# WL-AUDIO.net
KiCad netlist of a schematic drawn in Altium Designer
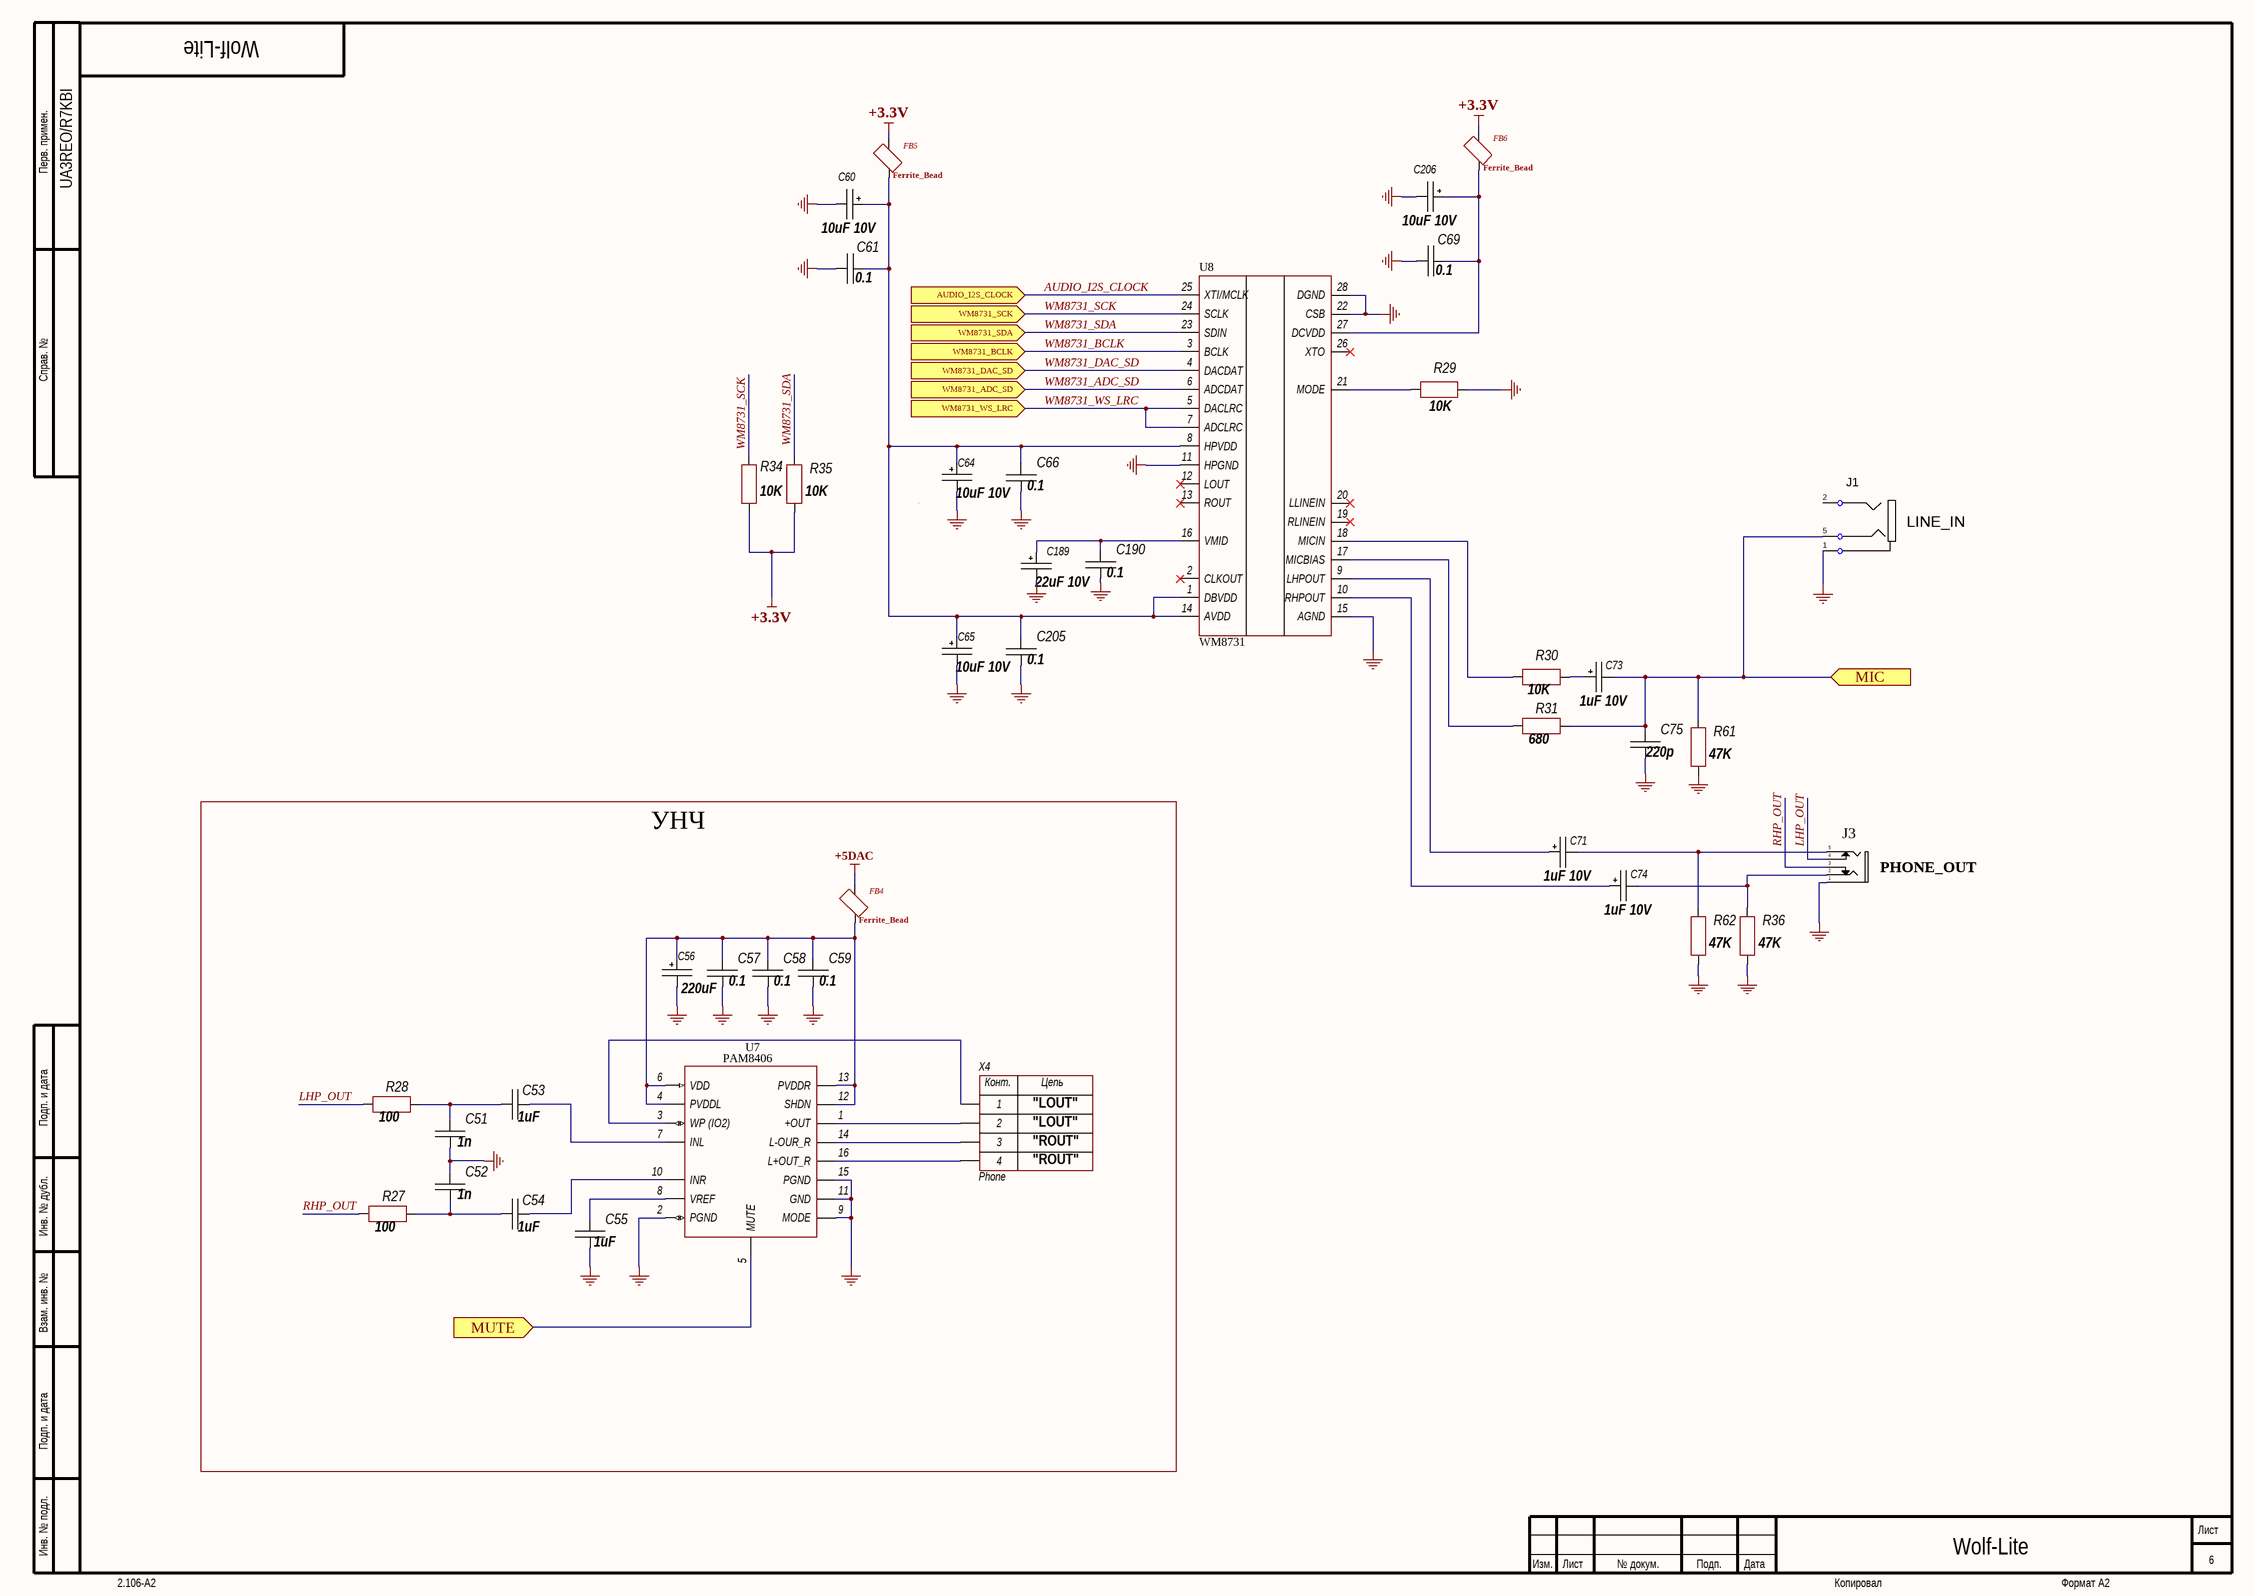
[diagram p0: WL-AUDIO.SchDoc]

(export (version "E")
  (design (tool "Eeschema 10.0.6"))
  (components
    (comp (ref "C51")
      (value "1n")
      (footprint "standard:CH0805C")
      (libsource (lib "Discrete") (part "Capacitor"))
    )
    (comp (ref "C52")
      (value "1n")
      (footprint "standard:CH0805C")
      (libsource (lib "Discrete") (part "Capacitor"))
    )
    (comp (ref "C53")
      (value "1uF")
      (footprint "standard:CH0805C")
      (libsource (lib "Discrete") (part "Capacitor"))
    )
    (comp (ref "C54")
      (value "1uF")
      (footprint "standard:CH0805C")
      (libsource (lib "Discrete") (part "Capacitor"))
    )
    (comp (ref "C55")
      (value "1uF")
      (footprint "standard:CH0805C")
      (libsource (lib "Discrete") (part "Capacitor"))
    )
    (comp (ref "C56") (value "220uF") (footprint "POLIMER-E") (libsource (lib "Discrete") (part "TantalCap")))
    (comp (ref "C57")
      (value "0.1")
      (footprint "standard:CH0805C")
      (libsource (lib "Discrete") (part "Capacitor"))
    )
    (comp (ref "C58")
      (value "0.1")
      (footprint "standard:CH0805C")
      (libsource (lib "Discrete") (part "Capacitor"))
    )
    (comp (ref "C59")
      (value "0.1")
      (footprint "standard:CH0805C")
      (libsource (lib "Discrete") (part "Capacitor"))
    )
    (comp (ref "C60")
      (value "10uF 10V")
      (footprint "standard:TANTAL_B")
      (libsource (lib "Discrete") (part "TantalCap"))
    )
    (comp (ref "C61")
      (value "0.1")
      (footprint "standard:CH0805C")
      (libsource (lib "Discrete") (part "Capacitor"))
    )
    (comp (ref "C64")
      (value "10uF 10V")
      (footprint "standard:TANTAL_B")
      (libsource (lib "Discrete") (part "TantalCap"))
    )
    (comp (ref "C65")
      (value "10uF 10V")
      (footprint "standard:TANTAL_B")
      (libsource (lib "Discrete") (part "TantalCap"))
    )
    (comp (ref "C66")
      (value "0.1")
      (footprint "standard:CH0805C")
      (libsource (lib "Discrete") (part "Capacitor"))
    )
    (comp (ref "C69")
      (value "0.1")
      (footprint "standard:CH0805C")
      (libsource (lib "Discrete") (part "Capacitor"))
    )
    (comp (ref "C71")
      (value "1uF 10V")
      (footprint "standard:TANTAL_A")
      (libsource (lib "Discrete") (part "TantalCap"))
    )
    (comp (ref "C73")
      (value "1uF 10V")
      (footprint "standard:TANTAL_A")
      (libsource (lib "Discrete") (part "TantalCap"))
    )
    (comp (ref "C74")
      (value "1uF 10V")
      (footprint "standard:TANTAL_A")
      (libsource (lib "Discrete") (part "TantalCap"))
    )
    (comp (ref "C75")
      (value "220p")
      (footprint "standard:CH0805C")
      (libsource (lib "Discrete") (part "Capacitor"))
    )
    (comp (ref "C189")
      (value "22uF 10V")
      (footprint "standard:TANTAL_B")
      (libsource (lib "Discrete") (part "TantalCap"))
    )
    (comp (ref "C190")
      (value "0.1")
      (footprint "standard:CH0805C")
      (libsource (lib "Discrete") (part "Capacitor"))
    )
    (comp (ref "C205")
      (value "0.1")
      (footprint "standard:CH0805C")
      (libsource (lib "Discrete") (part "Capacitor"))
    )
    (comp (ref "C206")
      (value "10uF 10V")
      (footprint "standard:TANTAL_B")
      (libsource (lib "Discrete") (part "TantalCap"))
    )
    (comp (ref "FB4") (value "Ferrite_Bead") (footprint "CH0805L") (libsource (lib "Discrete") (part "FB")))
    (comp (ref "FB5") (value "Ferrite_Bead") (footprint "CH0805L") (libsource (lib "Discrete") (part "FB")))
    (comp (ref "FB6") (value "Ferrite_Bead") (footprint "CH0805L") (libsource (lib "Discrete") (part "FB")))
    (comp (ref "J1")
      (value "LINE_IN")
      (footprint "3.5-stereo")
      (description "SJ1-3525NG")
      (libsource (lib "*") (part "SJ1-3523N"))
    )
    (comp (ref "J3") (value "PHONE_OUT") (footprint "3.5-stereo") (libsource (lib "SDR_ham") (part "PJ-3,5")))
    (comp (ref "R27")
      (value "100")
      (footprint "standard:CH0805R")
      (libsource (lib "Discrete") (part "Resistor"))
    )
    (comp (ref "R28")
      (value "100")
      (footprint "standard:CH0805R")
      (libsource (lib "Discrete") (part "Resistor"))
    )
    (comp (ref "R29")
      (value "10K")
      (footprint "standard:CH0805R")
      (libsource (lib "Discrete") (part "Resistor"))
    )
    (comp (ref "R30")
      (value "10K")
      (footprint "standard:CH0805R")
      (libsource (lib "Discrete") (part "Resistor"))
    )
    (comp (ref "R31")
      (value "680")
      (footprint "standard:CH0805R")
      (libsource (lib "Discrete") (part "Resistor"))
    )
    (comp (ref "R34") (value "10K") (footprint "standard:CH0805R") (libsource (lib "") (part "Resistor_1")))
    (comp (ref "R35") (value "10K") (footprint "standard:CH0805R") (libsource (lib "") (part "Resistor_1")))
    (comp (ref "R36") (value "47K") (footprint "standard:CH0805R") (libsource (lib "") (part "Resistor_1")))
    (comp (ref "R61") (value "47K") (footprint "standard:CH0805R") (libsource (lib "") (part "Resistor_1")))
    (comp (ref "R62") (value "47K") (footprint "standard:CH0805R") (libsource (lib "") (part "Resistor_1")))
    (comp (ref "U7") (value "PAM8406") (footprint "SOP-16") (libsource (lib "Digital") (part "PAM8406")))
    (comp (ref "U8") (value "WM8731") (footprint "28-SSOP") (libsource (lib "Digital") (part "WM8731")))
    (comp (ref "X4")
      (value "Phone")
      (footprint "custom:CON: CWF-4")
      (libsource (lib "Connectors") (part "4-Connector"))
    )
  )
  (nets
    (net (code "1") (name "+3.3V") (class "Default")
      (node (ref "FB5") (pin "2") (pinfunction "2_2") (pintype "passive"))
      (node (ref "FB6") (pin "2") (pinfunction "2_2") (pintype "passive"))
      (node (ref "R34") (pin "1") (pinfunction "1_1") (pintype "passive"))
      (node (ref "R35") (pin "1") (pinfunction "1_1") (pintype "passive"))
    )
    (net (code "2") (name "+5DAC") (class "Default")
      (node (ref "FB4") (pin "2") (pinfunction "2_2") (pintype "passive"))
    )
    (net (code "3") (name "/AUDIO_I2S_CLOCK") (class "Default")
      (node (ref "U8") (pin "25") (pinfunction "XTI/MCLK_25") (pintype "passive"))
    )
    (net (code "4") (name "/LHP_OUT") (class "Default")
      (node (ref "J3") (pin "4") (pinfunction "5_4") (pintype "passive"))
      (node (ref "R28") (pin "1") (pinfunction "1_1") (pintype "passive"))
    )
    (net (code "5") (name "/MIC") (class "Default")
      (node (ref "C73") (pin "2") (pinfunction "2_2") (pintype "power_in"))
      (node (ref "C75") (pin "1") (pinfunction "1_1") (pintype "power_in"))
      (node (ref "J1") (pin "5") (pinfunction "ring_5") (pintype "passive"))
      (node (ref "R31") (pin "2") (pinfunction "2_2") (pintype "passive"))
      (node (ref "R61") (pin "2") (pinfunction "2_2") (pintype "passive"))
    )
    (net (code "6") (name "/MUTE") (class "Default")
      (node (ref "U7") (pin "5") (pinfunction "MUTE_5") (pintype "passive"))
    )
    (net (code "7") (name "/RHP_OUT") (class "Default")
      (node (ref "J3") (pin "3") (pinfunction "6_3") (pintype "passive"))
      (node (ref "R27") (pin "1") (pinfunction "1_1") (pintype "passive"))
    )
    (net (code "8") (name "/WM8731_ADC_SD") (class "Default")
      (node (ref "U8") (pin "6") (pinfunction "ADCDAT_6") (pintype "passive"))
    )
    (net (code "9") (name "/WM8731_BCLK") (class "Default")
      (node (ref "U8") (pin "3") (pinfunction "BCLK_3") (pintype "passive"))
    )
    (net (code "10") (name "/WM8731_DAC_SD") (class "Default")
      (node (ref "U8") (pin "4") (pinfunction "DACDAT_4") (pintype "passive"))
    )
    (net (code "11") (name "/WM8731_SCK") (class "Default")
      (node (ref "R34") (pin "2") (pinfunction "2_2") (pintype "passive"))
      (node (ref "U8") (pin "24") (pinfunction "SCLK_24") (pintype "passive"))
    )
    (net (code "12") (name "/WM8731_SDA") (class "Default")
      (node (ref "R35") (pin "2") (pinfunction "2_2") (pintype "passive"))
      (node (ref "U8") (pin "23") (pinfunction "SDIN_23") (pintype "passive"))
    )
    (net (code "13") (name "/WM8731_WS_LRC") (class "Default")
      (node (ref "U8") (pin "5") (pinfunction "DACLRC_5") (pintype "passive"))
      (node (ref "U8") (pin "7") (pinfunction "ADCLRC_7") (pintype "passive"))
    )
    (net (code "14") (name "GND") (class "Default")
      (node (ref "C189") (pin "2") (pinfunction "2_2") (pintype "power_in"))
      (node (ref "C190") (pin "2") (pinfunction "2_2") (pintype "power_in"))
      (node (ref "C205") (pin "2") (pinfunction "2_2") (pintype "power_in"))
      (node (ref "C206") (pin "2") (pinfunction "2_2") (pintype "power_in"))
      (node (ref "C51") (pin "2") (pinfunction "2_2") (pintype "power_in"))
      (node (ref "C52") (pin "1") (pinfunction "1_1") (pintype "power_in"))
      (node (ref "C55") (pin "2") (pinfunction "2_2") (pintype "power_in"))
      (node (ref "C56") (pin "2") (pinfunction "2_2") (pintype "power_in"))
      (node (ref "C57") (pin "2") (pinfunction "2_2") (pintype "power_in"))
      (node (ref "C58") (pin "2") (pinfunction "2_2") (pintype "power_in"))
      (node (ref "C59") (pin "2") (pinfunction "2_2") (pintype "power_in"))
      (node (ref "C60") (pin "2") (pinfunction "2_2") (pintype "power_in"))
      (node (ref "C61") (pin "2") (pinfunction "2_2") (pintype "power_in"))
      (node (ref "C64") (pin "2") (pinfunction "2_2") (pintype "power_in"))
      (node (ref "C65") (pin "2") (pinfunction "2_2") (pintype "power_in"))
      (node (ref "C66") (pin "2") (pinfunction "2_2") (pintype "power_in"))
      (node (ref "C69") (pin "2") (pinfunction "2_2") (pintype "power_in"))
      (node (ref "C75") (pin "2") (pinfunction "2_2") (pintype "power_in"))
      (node (ref "J1") (pin "1") (pinfunction "sleeve_1") (pintype "passive"))
      (node (ref "J3") (pin "1") (pinfunction "8_1") (pintype "passive"))
      (node (ref "R29") (pin "2") (pinfunction "2_2") (pintype "passive"))
      (node (ref "R36") (pin "1") (pinfunction "1_1") (pintype "passive"))
      (node (ref "R61") (pin "1") (pinfunction "1_1") (pintype "passive"))
      (node (ref "R62") (pin "1") (pinfunction "1_1") (pintype "passive"))
      (node (ref "U7") (pin "11") (pinfunction "GND_11") (pintype "passive"))
      (node (ref "U7") (pin "15") (pinfunction "PGND_15") (pintype "passive"))
      (node (ref "U7") (pin "2") (pinfunction "PGND_2") (pintype "bidirectional"))
      (node (ref "U7") (pin "9") (pinfunction "MODE_9") (pintype "passive"))
      (node (ref "U8") (pin "11") (pinfunction "HPGND_11") (pintype "passive"))
      (node (ref "U8") (pin "15") (pinfunction "AGND_15") (pintype "passive"))
      (node (ref "U8") (pin "22") (pinfunction "CSB_22") (pintype "passive"))
      (node (ref "U8") (pin "28") (pinfunction "DGND_28") (pintype "passive"))
    )
    (net (code "15") (name "Net-(C51-Pad1)") (class "Default")
      (node (ref "C51") (pin "1") (pinfunction "1_1") (pintype "power_in"))
      (node (ref "C53") (pin "1") (pinfunction "1_1") (pintype "power_in"))
      (node (ref "R28") (pin "2") (pinfunction "2_2") (pintype "passive"))
    )
    (net (code "16") (name "Net-(C52-Pad2)") (class "Default")
      (node (ref "C52") (pin "2") (pinfunction "2_2") (pintype "power_in"))
      (node (ref "C54") (pin "1") (pinfunction "1_1") (pintype "power_in"))
      (node (ref "R27") (pin "2") (pinfunction "2_2") (pintype "passive"))
    )
    (net (code "17") (name "Net-(C73-Pad1)") (class "Default")
      (node (ref "C73") (pin "1") (pinfunction "1_1") (pintype "power_in"))
      (node (ref "R30") (pin "2") (pinfunction "2_2") (pintype "passive"))
    )
    (net (code "18") (name "Net-(J3-4)") (class "Default")
      (node (ref "C71") (pin "2") (pinfunction "2_2") (pintype "power_in"))
      (node (ref "J3") (pin "5") (pinfunction "4_5") (pintype "passive"))
      (node (ref "R62") (pin "2") (pinfunction "2_2") (pintype "passive"))
    )
    (net (code "19") (name "Net-(J3-7)") (class "Default")
      (node (ref "C74") (pin "2") (pinfunction "2_2") (pintype "power_in"))
      (node (ref "J3") (pin "2") (pinfunction "7_2") (pintype "passive"))
      (node (ref "R36") (pin "2") (pinfunction "2_2") (pintype "passive"))
    )
    (net (code "20") (name "Net-(U7-+OUT)") (class "Default")
      (node (ref "U7") (pin "1") (pinfunction "+OUT_1") (pintype "passive"))
      (node (ref "X4") (pin "2") (pinfunction "2_2") (pintype "passive"))
    )
    (net (code "21") (name "Net-(U7-INL)") (class "Default")
      (node (ref "C53") (pin "2") (pinfunction "2_2") (pintype "power_in"))
      (node (ref "U7") (pin "7") (pinfunction "INL_7") (pintype "passive"))
    )
    (net (code "22") (name "Net-(U7-INR)") (class "Default")
      (node (ref "C54") (pin "2") (pinfunction "2_2") (pintype "power_in"))
      (node (ref "U7") (pin "10") (pinfunction "INR_10") (pintype "passive"))
    )
    (net (code "23") (name "Net-(U7-L+OUT_R)") (class "Default")
      (node (ref "U7") (pin "16") (pinfunction "L+OUT_R_16") (pintype "passive"))
      (node (ref "X4") (pin "4") (pinfunction "4_4") (pintype "power_in"))
    )
    (net (code "24") (name "Net-(U7-L-OUR_R)") (class "Default")
      (node (ref "U7") (pin "14") (pinfunction "L-OUR_R_14") (pintype "passive"))
      (node (ref "X4") (pin "3") (pinfunction "3_3") (pintype "power_in"))
    )
    (net (code "25") (name "Net-(U7-PVDDL)") (class "Default")
      (node (ref "C56") (pin "1") (pinfunction "1_1") (pintype "power_in"))
      (node (ref "C57") (pin "1") (pinfunction "1_1") (pintype "power_in"))
      (node (ref "C58") (pin "1") (pinfunction "1_1") (pintype "power_in"))
      (node (ref "C59") (pin "1") (pinfunction "1_1") (pintype "power_in"))
      (node (ref "FB4") (pin "1") (pinfunction "1_1") (pintype "passive"))
      (node (ref "U7") (pin "12") (pinfunction "SHDN_12") (pintype "passive"))
      (node (ref "U7") (pin "13") (pinfunction "PVDDR_13") (pintype "passive"))
      (node (ref "U7") (pin "4") (pinfunction "PVDDL_4") (pintype "power_in"))
      (node (ref "U7") (pin "6") (pinfunction "VDD_6") (pintype "input"))
    )
    (net (code "26") (name "Net-(U7-VREF)") (class "Default")
      (node (ref "C55") (pin "1") (pinfunction "1_1") (pintype "power_in"))
      (node (ref "U7") (pin "8") (pinfunction "VREF_8") (pintype "power_in"))
    )
    (net (code "27") (name "Net-(U7-WP_(IO2))") (class "Default")
      (node (ref "U7") (pin "3") (pinfunction "WP_(IO2)_3") (pintype "bidirectional"))
      (node (ref "X4") (pin "1") (pinfunction "1_1") (pintype "passive"))
    )
    (net (code "28") (name "Net-(U8-AVDD)") (class "Default")
      (node (ref "C205") (pin "1") (pinfunction "1_1") (pintype "power_in"))
      (node (ref "C60") (pin "1") (pinfunction "1_1") (pintype "power_in"))
      (node (ref "C61") (pin "1") (pinfunction "1_1") (pintype "power_in"))
      (node (ref "C64") (pin "1") (pinfunction "1_1") (pintype "power_in"))
      (node (ref "C65") (pin "1") (pinfunction "1_1") (pintype "power_in"))
      (node (ref "C66") (pin "1") (pinfunction "1_1") (pintype "power_in"))
      (node (ref "FB5") (pin "1") (pinfunction "1_1") (pintype "passive"))
      (node (ref "U8") (pin "1") (pinfunction "DBVDD_1") (pintype "passive"))
      (node (ref "U8") (pin "14") (pinfunction "AVDD_14") (pintype "passive"))
      (node (ref "U8") (pin "8") (pinfunction "HPVDD_8") (pintype "passive"))
    )
    (net (code "29") (name "Net-(U8-DCVDD)") (class "Default")
      (node (ref "C206") (pin "1") (pinfunction "1_1") (pintype "power_in"))
      (node (ref "C69") (pin "1") (pinfunction "1_1") (pintype "power_in"))
      (node (ref "FB6") (pin "1") (pinfunction "1_1") (pintype "passive"))
      (node (ref "U8") (pin "27") (pinfunction "DCVDD_27") (pintype "passive"))
    )
    (net (code "30") (name "Net-(U8-LHPOUT)") (class "Default")
      (node (ref "C71") (pin "1") (pinfunction "1_1") (pintype "power_in"))
      (node (ref "U8") (pin "9") (pinfunction "LHPOUT_9") (pintype "passive"))
    )
    (net (code "31") (name "Net-(U8-MICBIAS)") (class "Default")
      (node (ref "R31") (pin "1") (pinfunction "1_1") (pintype "passive"))
      (node (ref "U8") (pin "17") (pinfunction "MICBIAS_17") (pintype "passive"))
    )
    (net (code "32") (name "Net-(U8-MICIN)") (class "Default")
      (node (ref "R30") (pin "1") (pinfunction "1_1") (pintype "passive"))
      (node (ref "U8") (pin "18") (pinfunction "MICIN_18") (pintype "passive"))
    )
    (net (code "33") (name "Net-(U8-MODE)") (class "Default")
      (node (ref "R29") (pin "1") (pinfunction "1_1") (pintype "passive"))
      (node (ref "U8") (pin "21") (pinfunction "MODE_21") (pintype "passive"))
    )
    (net (code "34") (name "Net-(U8-RHPOUT)") (class "Default")
      (node (ref "C74") (pin "1") (pinfunction "1_1") (pintype "power_in"))
      (node (ref "U8") (pin "10") (pinfunction "RHPOUT_10") (pintype "passive"))
    )
    (net (code "35") (name "Net-(U8-VMID)") (class "Default")
      (node (ref "C189") (pin "1") (pinfunction "1_1") (pintype "power_in"))
      (node (ref "C190") (pin "1") (pinfunction "1_1") (pintype "power_in"))
      (node (ref "U8") (pin "16") (pinfunction "VMID_16") (pintype "passive"))
    )
    (net (code "36") (name "unconnected-(J1-tip-Pad2)") (class "Default")
      (node (ref "J1") (pin "2") (pinfunction "tip_2") (pintype "passive"))
    )
    (net (code "37") (name "unconnected-(U8-CLKOUT-Pad2)") (class "Default")
      (node (ref "U8") (pin "2") (pinfunction "CLKOUT_2") (pintype "passive+no_connect"))
    )
    (net (code "38") (name "unconnected-(U8-LLINEIN-Pad20)") (class "Default")
      (node (ref "U8") (pin "20") (pinfunction "LLINEIN_20") (pintype "passive+no_connect"))
    )
    (net (code "39") (name "unconnected-(U8-LOUT-Pad12)") (class "Default")
      (node (ref "U8") (pin "12") (pinfunction "LOUT_12") (pintype "passive+no_connect"))
    )
    (net (code "40") (name "unconnected-(U8-RLINEIN-Pad19)") (class "Default")
      (node (ref "U8") (pin "19") (pinfunction "RLINEIN_19") (pintype "passive+no_connect"))
    )
    (net (code "41") (name "unconnected-(U8-ROUT-Pad13)") (class "Default")
      (node (ref "U8") (pin "13") (pinfunction "ROUT_13") (pintype "passive+no_connect"))
    )
    (net (code "42") (name "unconnected-(U8-XTO-Pad26)") (class "Default")
      (node (ref "U8") (pin "26") (pinfunction "XTO_26") (pintype "passive+no_connect"))
    )
  )
)
